# Audio.net
KiCad netlist of a schematic drawn in Altium Designer
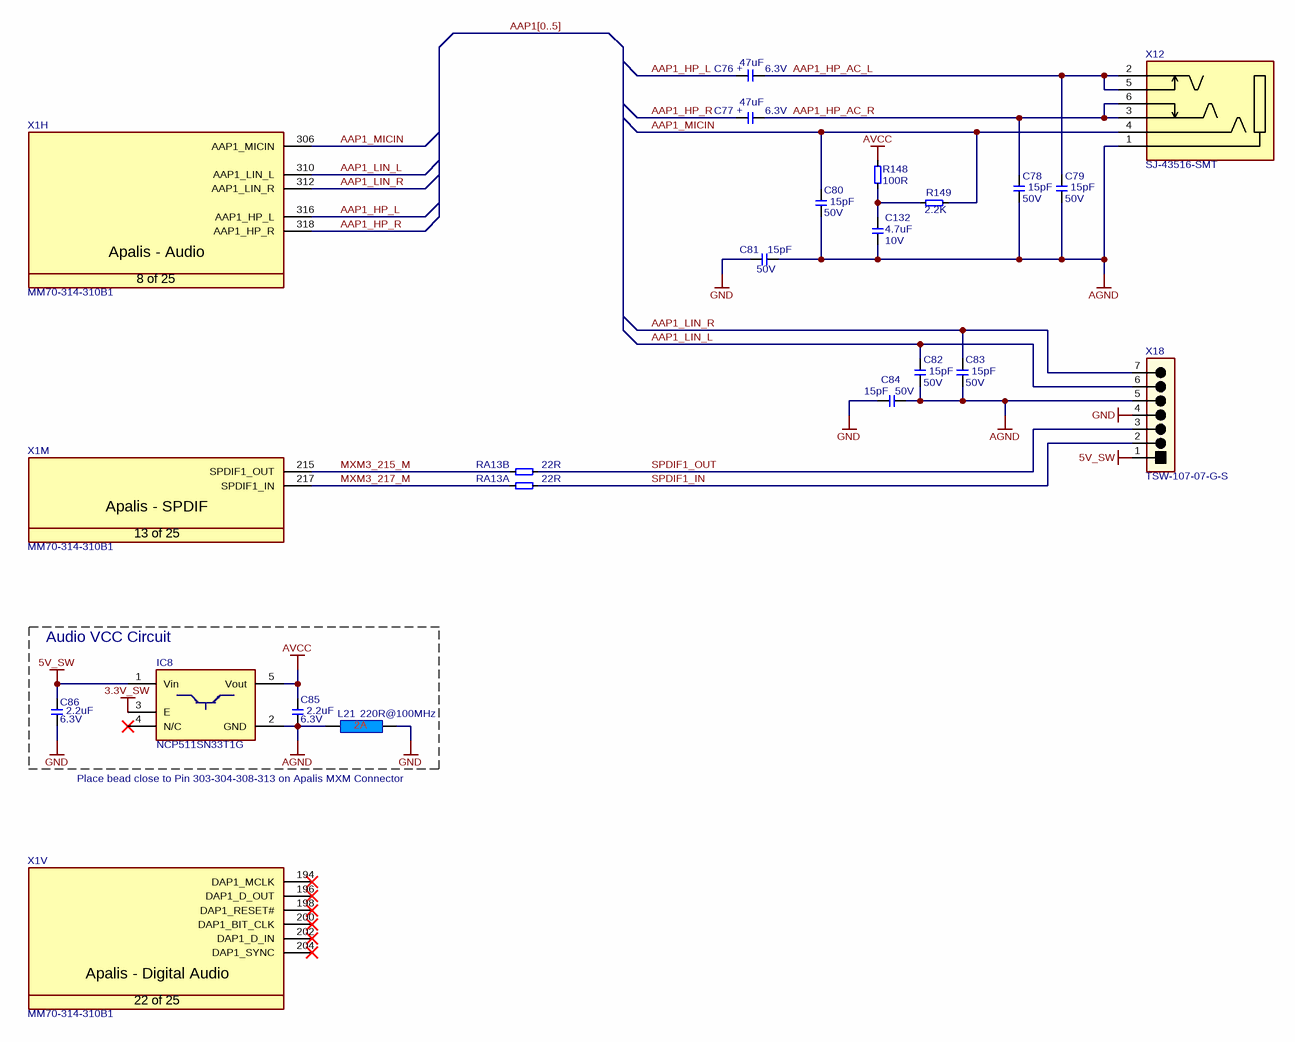
[diagram p0: Audio.SchDoc]

(export (version "E")
  (design (tool "Eeschema 10.0.6"))
  (components
    (comp (ref "C76")
      (value "47uF")
      (footprint "T_CAPMP3216X180N")
      (description "Capacitor TA 47uF 6.3V 20% 3216")
      (fields (field (name "TOLERANCE") "20%") (field (name "RATING") "6.3V"))
      (libsource (lib "Ixora") (part "C-TA-47uF-6.3V-20%-3216"))
    )
    (comp (ref "C77")
      (value "47uF")
      (footprint "T_CAPMP3216X180N")
      (description "Capacitor TA 47uF 6.3V 20% 3216")
      (fields (field (name "TOLERANCE") "20%") (field (name "RATING") "6.3V"))
      (libsource (lib "Ixora") (part "C-TA-47uF-6.3V-20%-3216"))
    )
    (comp (ref "C78")
      (value "15pF")
      (footprint "T_CAPC0603X33N")
      (description "Capacitor Ceramic NP0 15pF 50V 10% 0603")
      (fields (field (name "TOLERANCE") "10%") (field (name "RATING") "50V"))
      (libsource (lib "Ixora") (part "C-NP0-15pF-50V-10%-0603"))
    )
    (comp (ref "C79")
      (value "15pF")
      (footprint "T_CAPC0603X33N")
      (description "Capacitor Ceramic NP0 15pF 50V 10% 0603")
      (fields (field (name "TOLERANCE") "10%") (field (name "RATING") "50V"))
      (libsource (lib "Ixora") (part "C-NP0-15pF-50V-10%-0603"))
    )
    (comp (ref "C80")
      (value "15pF")
      (footprint "T_CAPC0603X33N")
      (description "Capacitor Ceramic NP0 15pF 50V 10% 0603")
      (fields (field (name "TOLERANCE") "10%") (field (name "RATING") "50V"))
      (libsource (lib "Ixora") (part "C-NP0-15pF-50V-10%-0603"))
    )
    (comp (ref "C81")
      (value "15pF")
      (footprint "T_CAPC0603X33N")
      (description "Capacitor Ceramic NP0 15pF 50V 10% 0603")
      (fields (field (name "TOLERANCE") "10%") (field (name "RATING") "50V"))
      (libsource (lib "Ixora") (part "C-NP0-15pF-50V-10%-0603"))
    )
    (comp (ref "C82")
      (value "15pF")
      (footprint "T_CAPC0603X33N")
      (description "Capacitor Ceramic NP0 15pF 50V 10% 0603")
      (fields (field (name "TOLERANCE") "10%") (field (name "RATING") "50V"))
      (libsource (lib "Ixora") (part "C-NP0-15pF-50V-10%-0603"))
    )
    (comp (ref "C83")
      (value "15pF")
      (footprint "T_CAPC0603X33N")
      (description "Capacitor Ceramic NP0 15pF 50V 10% 0603")
      (fields (field (name "TOLERANCE") "10%") (field (name "RATING") "50V"))
      (libsource (lib "Ixora") (part "C-NP0-15pF-50V-10%-0603"))
    )
    (comp (ref "C84")
      (value "15pF")
      (footprint "T_CAPC0603X33N")
      (description "Capacitor Ceramic NP0 15pF 50V 10% 0603")
      (fields (field (name "TOLERANCE") "10%") (field (name "RATING") "50V"))
      (libsource (lib "Ixora") (part "C-NP0-15pF-50V-10%-0603"))
    )
    (comp (ref "C85")
      (value "2.2uF")
      (footprint "T_CAPC0603X33N")
      (description "Capacitor Ceramic X5R 2.2uF 6.3V 20% 0603")
      (fields (field (name "TOLERANCE") "20%") (field (name "RATING") "6.3V"))
      (libsource (lib "Ixora") (part "C-X5R-2.2uF-6.3V-20%-0603"))
    )
    (comp (ref "C86")
      (value "2.2uF")
      (footprint "T_CAPC0603X33N")
      (description "Capacitor Ceramic X5R 2.2uF 6.3V 20% 0603")
      (fields (field (name "TOLERANCE") "20%") (field (name "RATING") "6.3V"))
      (libsource (lib "Ixora") (part "C-X5R-2.2uF-6.3V-20%-0603"))
    )
    (comp (ref "C132")
      (value "4.7uF")
      (footprint "T_CAPC0603X33N")
      (description "Capacitor Ceramic X5R 4.7uF 10V 10% 0603")
      (fields (field (name "TOLERANCE") "10%") (field (name "RATING") "10V"))
      (libsource (lib "Ixora") (part "C-X5R-4.7uF-10V-10%-0603"))
    )
    (comp (ref "IC8")
      (value "NCP511SN33T1G")
      (footprint "SOT95P279X142-5N")
      (description "NCP511SN33T1G LDO Regulator")
      (fields (field (name "MANUFACTURER PART NO.") "NCP511SN33T1G"))
      (libsource (lib "Ixora") (part "IC-ON-NCP511SN33T1G"))
    )
    (comp (ref "L21")
      (value "220R@100MHz")
      (footprint "INDC1608X95N")
      (description "220R@100MHz 2A EMI FILTER")
      (fields (field (name "TOLERANCE") "25%"))
      (libsource (lib "Ixora") (part "L-220R@100MHz-2A-25%-0603"))
    )
    (comp (ref "R148")
      (value "100R")
      (footprint "RESC1005X40N")
      (description "Resistor 100 ohm 63mW 5% 0402")
      (fields (field (name "TOLERANCE") "5%"))
      (libsource (lib "Ixora") (part "R-100R-63mW-5%-0402"))
    )
    (comp (ref "R149")
      (value "2.2K")
      (footprint "RESC1005X40N")
      (description "Resistor 2.2Kohm 63mW 5% 0402")
      (fields (field (name "TOLERANCE") "5%"))
      (libsource (lib "Ixora") (part "R-2.2KR-63mW-5%-0402"))
    )
    (comp (ref "RA13")
      (value "22R")
      (footprint "T_Resistor_Array_X4")
      (description "Resistor Array 22 R 63mW 5% 1206")
      (fields (field (name "TOLERANCE") "5%"))
      (libsource (lib "Ixora") (part "RA-22R-63mW-5%-1206-div"))
    )
    (comp (ref "X1")
      (value "CON-JAE-MM70-314-310B1-314-0.5mm")
      (footprint "T_JAE_MM70-314-310B1")
      (description "MXM3 Connector")
      (fields (field (name "MANUFACTURER PART NO.") "MM70-314-310B1"))
      (libsource (lib "Ixora") (part "CON-JAE-MM70-314-310B1-314-0.5mm"))
    )
    (comp (ref "X12")
      (value "SJ-43516-SMT")
      (footprint "T_CI_SJ-43516-SMT")
      (description "3.5mm Stereo Jack SMD With Detect Contact")
      (fields (field (name "MANUFACTURER PART NO.") "SJ-43516-SMT"))
      (libsource (lib "Ixora") (part "CON-Cui-SJ-43516-SMT-6-3.5mm"))
    )
    (comp (ref "X18")
      (value "TSW-107-07-G-S")
      (footprint "T_samtech_TSW-107-07-G-S")
      (description "Header male, 1X7 Pins, 2.54 mm pitch")
      (fields (field (name "MANUFACTURER PART NO.") "TSW-107-07-G-S"))
      (libsource (lib "Ixora") (part "CON-Samtec-TSW-107-07-G-S"))
    )
  )
  (nets
    (net (code "8") (name "/AAP1_HP_AC_L") (class "Default")
      (node (ref "C76") (pin "2") (pinfunction "2_2") (pintype "passive"))
      (node (ref "C79") (pin "2") (pinfunction "2_2") (pintype "passive"))
      (node (ref "X12") (pin "2") (pinfunction "2_2") (pintype "passive"))
      (node (ref "X12") (pin "5") (pinfunction "5_5") (pintype "passive"))
    )
    (net (code "9") (name "/AAP1_HP_AC_R") (class "Default")
      (node (ref "C77") (pin "2") (pinfunction "2_2") (pintype "passive"))
      (node (ref "C78") (pin "2") (pinfunction "2_2") (pintype "passive"))
      (node (ref "X12") (pin "3") (pinfunction "3_3") (pintype "passive"))
      (node (ref "X12") (pin "6") (pinfunction "6_6") (pintype "passive"))
    )
    (net (code "10") (name "/AAP1_HP_L") (class "Default")
      (node (ref "C76") (pin "1") (pinfunction "1_1") (pintype "passive"))
      (node (ref "X1") (pin "316") (pinfunction "AAP1_HP_L_316") (pintype "passive"))
    )
    (net (code "11") (name "/AAP1_HP_R") (class "Default")
      (node (ref "C77") (pin "1") (pinfunction "1_1") (pintype "passive"))
      (node (ref "X1") (pin "318") (pinfunction "AAP1_HP_R_318") (pintype "passive"))
    )
    (net (code "12") (name "/AAP1_LIN_L") (class "Default")
      (node (ref "C82") (pin "2") (pinfunction "2_2") (pintype "passive"))
      (node (ref "X1") (pin "310") (pinfunction "AAP1_LIN_L_310") (pintype "passive"))
      (node (ref "X18") (pin "6") (pinfunction "6_6") (pintype "passive"))
    )
    (net (code "13") (name "/AAP1_LIN_R") (class "Default")
      (node (ref "C83") (pin "2") (pinfunction "2_2") (pintype "passive"))
      (node (ref "X1") (pin "312") (pinfunction "AAP1_LIN_R_312") (pintype "passive"))
      (node (ref "X18") (pin "7") (pinfunction "7_7") (pintype "passive"))
    )
    (net (code "14") (name "/AAP1_MICIN") (class "Default")
      (node (ref "C80") (pin "2") (pinfunction "2_2") (pintype "passive"))
      (node (ref "R149") (pin "1") (pinfunction "1_1") (pintype "passive"))
      (node (ref "X1") (pin "306") (pinfunction "AAP1_MICIN_306") (pintype "passive"))
      (node (ref "X12") (pin "4") (pinfunction "4_4") (pintype "passive"))
    )
    (net (code "15") (name "/MXM3_215_M") (class "Default")
      (node (ref "RA13") (pin "2") (pinfunction "2_2") (pintype "passive"))
      (node (ref "X1") (pin "215") (pinfunction "SPDIF1_OUT_215") (pintype "passive"))
    )
    (net (code "16") (name "/MXM3_217_M") (class "Default")
      (node (ref "RA13") (pin "1") (pinfunction "1_1") (pintype "passive"))
      (node (ref "X1") (pin "217") (pinfunction "SPDIF1_IN_217") (pintype "passive"))
    )
    (net (code "17") (name "/SPDIF1_IN") (class "Default")
      (node (ref "RA13") (pin "5") (pinfunction "5_5") (pintype "passive"))
      (node (ref "X18") (pin "2") (pinfunction "2_2") (pintype "passive"))
    )
    (net (code "18") (name "/SPDIF1_OUT") (class "Default")
      (node (ref "RA13") (pin "6") (pinfunction "6_6") (pintype "passive"))
      (node (ref "X18") (pin "3") (pinfunction "3_3") (pintype "passive"))
    )
    (net (code "19") (name "3.3V_SW") (class "Default")
      (node (ref "IC8") (pin "3") (pinfunction "E_3") (pintype "passive"))
    )
    (net (code "20") (name "5V_SW") (class "Default")
      (node (ref "C86") (pin "2") (pinfunction "2_2") (pintype "passive"))
      (node (ref "IC8") (pin "1") (pinfunction "Vin_1") (pintype "passive"))
      (node (ref "X18") (pin "1") (pinfunction "1_1") (pintype "passive"))
    )
    (net (code "21") (name "AGND") (class "Default")
      (node (ref "C132") (pin "2") (pinfunction "2_2") (pintype "passive"))
      (node (ref "C78") (pin "1") (pinfunction "1_1") (pintype "passive"))
      (node (ref "C79") (pin "1") (pinfunction "1_1") (pintype "passive"))
      (node (ref "C80") (pin "1") (pinfunction "1_1") (pintype "passive"))
      (node (ref "C81") (pin "2") (pinfunction "2_2") (pintype "passive"))
      (node (ref "C82") (pin "1") (pinfunction "1_1") (pintype "passive"))
      (node (ref "C83") (pin "1") (pinfunction "1_1") (pintype "passive"))
      (node (ref "C84") (pin "2") (pinfunction "2_2") (pintype "passive"))
      (node (ref "C85") (pin "1") (pinfunction "1_1") (pintype "passive"))
      (node (ref "IC8") (pin "2") (pinfunction "GND_2") (pintype "passive"))
      (node (ref "L21") (pin "1") (pinfunction "1_1") (pintype "passive"))
      (node (ref "X12") (pin "1") (pinfunction "1_1") (pintype "passive"))
      (node (ref "X18") (pin "5") (pinfunction "5_5") (pintype "passive"))
    )
    (net (code "22") (name "AVCC") (class "Default")
      (node (ref "C85") (pin "2") (pinfunction "2_2") (pintype "passive"))
      (node (ref "IC8") (pin "5") (pinfunction "Vout_5") (pintype "passive"))
      (node (ref "R148") (pin "2") (pinfunction "2_2") (pintype "passive"))
    )
    (net (code "23") (name "GND") (class "Default")
      (node (ref "C81") (pin "1") (pinfunction "1_1") (pintype "passive"))
      (node (ref "C84") (pin "1") (pinfunction "1_1") (pintype "passive"))
      (node (ref "C86") (pin "1") (pinfunction "1_1") (pintype "passive"))
      (node (ref "L21") (pin "2") (pinfunction "2_2") (pintype "passive"))
      (node (ref "X18") (pin "4") (pinfunction "4_4") (pintype "passive"))
    )
    (net (code "24") (name "Net-(C132-Pad1)") (class "Default")
      (node (ref "C132") (pin "1") (pinfunction "1_1") (pintype "passive"))
      (node (ref "R148") (pin "1") (pinfunction "1_1") (pintype "passive"))
      (node (ref "R149") (pin "2") (pinfunction "2_2") (pintype "passive"))
    )
    (net (code "25") (name "unconnected-(IC8-N{slash}C-Pad4)") (class "Default")
      (node (ref "IC8") (pin "4") (pinfunction "N/C_4") (pintype "passive+no_connect"))
    )
    (net (code "26") (name "unconnected-(X1V-DAP1_BIT_CLK-Pad200)") (class "Default")
      (node (ref "X1") (pin "200") (pinfunction "DAP1_BIT_CLK_200") (pintype "passive+no_connect"))
    )
    (net (code "27") (name "unconnected-(X1V-DAP1_D_IN-Pad202)") (class "Default")
      (node (ref "X1") (pin "202") (pinfunction "DAP1_D_IN_202") (pintype "passive+no_connect"))
    )
    (net (code "28") (name "unconnected-(X1V-DAP1_D_OUT-Pad196)") (class "Default")
      (node (ref "X1") (pin "196") (pinfunction "DAP1_D_OUT_196") (pintype "passive+no_connect"))
    )
    (net (code "29") (name "unconnected-(X1V-DAP1_MCLK-Pad194)") (class "Default")
      (node (ref "X1") (pin "194") (pinfunction "DAP1_MCLK_194") (pintype "passive+no_connect"))
    )
    (net (code "30") (name "unconnected-(X1V-DAP1_RESET#-Pad198)") (class "Default")
      (node (ref "X1") (pin "198") (pinfunction "DAP1_RESET#_198") (pintype "passive+no_connect"))
    )
    (net (code "31") (name "unconnected-(X1V-DAP1_SYNC-Pad204)") (class "Default")
      (node (ref "X1") (pin "204") (pinfunction "DAP1_SYNC_204") (pintype "passive+no_connect"))
    )
  )
)
